# FInk.net
KiCad netlist of a schematic drawn in Altium Designer
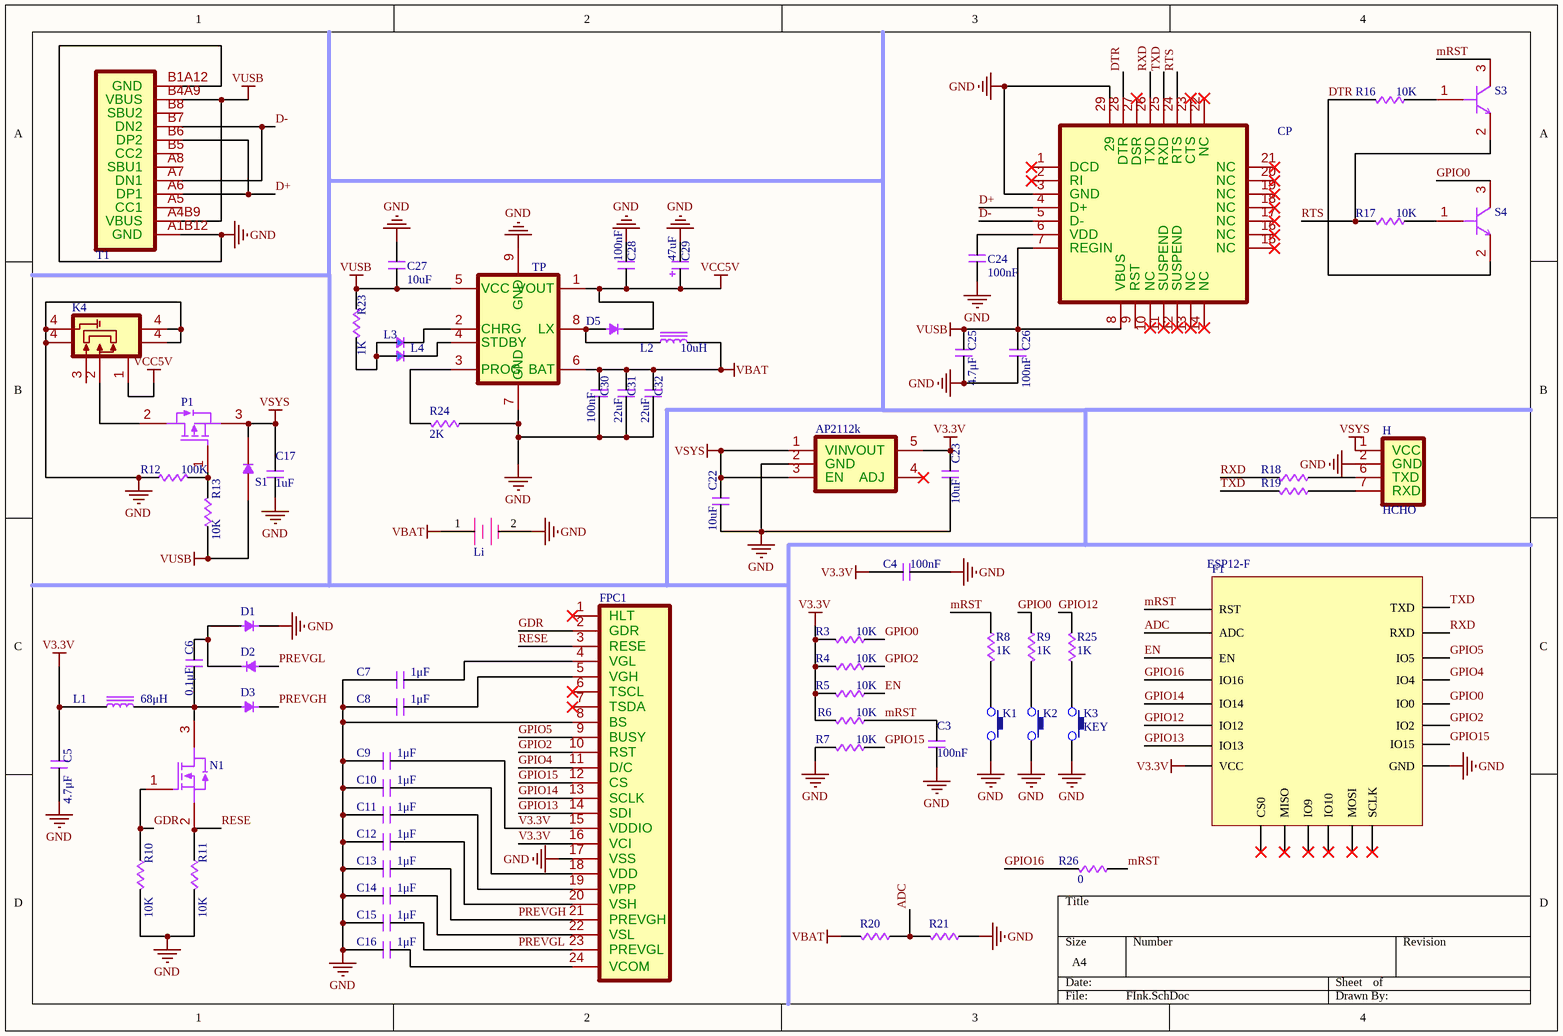
[diagram p0: FInk.SchDoc]

(export (version "E")
  (design (tool "Eeschema 10.0.6"))
  (components
    (comp (ref "AP2112k")
      (value "SPX3819 电源芯片")
      (footprint "SOT_23_SPX3819")
      (libsource (lib "Integrated_Library") (part "SPX3819 电源芯片"))
    )
    (comp (ref "C3")
      (value "100nF")
      (footprint "0603_C")
      (fields (field (name "Comment") "0603_C"))
      (libsource (lib "") (part "0603_C_1"))
    )
    (comp (ref "C4")
      (value "100nF")
      (footprint "0603_C")
      (fields (field (name "Comment") "0603_C"))
      (libsource (lib "Integrated_Library") (part "0603_C"))
    )
    (comp (ref "C5")
      (value "4.7μF")
      (footprint "0603_C")
      (fields (field (name "Comment") "0603_C"))
      (libsource (lib "") (part "0603_C_1"))
    )
    (comp (ref "C6")
      (value "0.1μF")
      (footprint "0603_C")
      (fields (field (name "Comment") "0603_C"))
      (libsource (lib "") (part "0603_C_1"))
    )
    (comp (ref "C7")
      (value "1μF")
      (footprint "0603_C")
      (fields (field (name "Comment") "0603_C"))
      (libsource (lib "Integrated_Library") (part "0603_C"))
    )
    (comp (ref "C8")
      (value "1μF")
      (footprint "0603_C")
      (fields (field (name "Comment") "0603_C"))
      (libsource (lib "Integrated_Library") (part "0603_C"))
    )
    (comp (ref "C9")
      (value "1μF")
      (footprint "0603_C")
      (fields (field (name "Comment") "0603_C"))
      (libsource (lib "Integrated_Library") (part "0603_C"))
    )
    (comp (ref "C10")
      (value "1μF")
      (footprint "0603_C")
      (fields (field (name "Comment") "0603_C"))
      (libsource (lib "Integrated_Library") (part "0603_C"))
    )
    (comp (ref "C11")
      (value "1μF")
      (footprint "0603_C")
      (fields (field (name "Comment") "0603_C"))
      (libsource (lib "Integrated_Library") (part "0603_C"))
    )
    (comp (ref "C12")
      (value "1μF")
      (footprint "0603_C")
      (fields (field (name "Comment") "0603_C"))
      (libsource (lib "Integrated_Library") (part "0603_C"))
    )
    (comp (ref "C13")
      (value "1μF")
      (footprint "0603_C")
      (fields (field (name "Comment") "0603_C"))
      (libsource (lib "Integrated_Library") (part "0603_C"))
    )
    (comp (ref "C14")
      (value "1μF")
      (footprint "0603_C")
      (fields (field (name "Comment") "0603_C"))
      (libsource (lib "Integrated_Library") (part "0603_C"))
    )
    (comp (ref "C15")
      (value "1μF")
      (footprint "0603_C")
      (fields (field (name "Comment") "0603_C"))
      (libsource (lib "Integrated_Library") (part "0603_C"))
    )
    (comp (ref "C16")
      (value "1μF")
      (footprint "0603_C")
      (fields (field (name "Comment") "0603_C"))
      (libsource (lib "Integrated_Library") (part "0603_C"))
    )
    (comp (ref "C17")
      (value "1uF")
      (footprint "0603_C")
      (fields (field (name "Comment") "0603_C"))
      (libsource (lib "") (part "0603_C_1"))
    )
    (comp (ref "C22")
      (value "10uF")
      (footprint "0603_C")
      (fields (field (name "Comment") "0603_C"))
      (libsource (lib "") (part "0603_C_1"))
    )
    (comp (ref "C23")
      (value "10uF")
      (footprint "0603_C")
      (fields (field (name "Comment") "0603_C"))
      (libsource (lib "") (part "0603_C_1"))
    )
    (comp (ref "C24")
      (value "100nF")
      (footprint "0603_C")
      (fields (field (name "Comment") "0603_C"))
      (libsource (lib "") (part "0603_C_1"))
    )
    (comp (ref "C25")
      (value "4.7μF")
      (footprint "0603_C")
      (fields (field (name "Comment") "0603_C"))
      (libsource (lib "") (part "0603_C_1"))
    )
    (comp (ref "C26")
      (value "100nF")
      (footprint "0603_C")
      (fields (field (name "Comment") "0603_C"))
      (libsource (lib "") (part "0603_C_1"))
    )
    (comp (ref "C27")
      (value "10uF")
      (footprint "0603_C")
      (fields (field (name "Comment") "0603_C"))
      (libsource (lib "") (part "0603_C_1"))
    )
    (comp (ref "C28")
      (value "100nF")
      (footprint "0603_C")
      (fields (field (name "Comment") "0603_C"))
      (libsource (lib "") (part "0603_C_1"))
    )
    (comp (ref "C29")
      (value "47uF")
      (footprint "A_CASE_c")
      (fields (field (name "Comment") "A_CASE_C"))
      (libsource (lib "Integrated_Library") (part "A_CASE_C"))
    )
    (comp (ref "C30")
      (value "100nF")
      (footprint "0603_C")
      (fields (field (name "Comment") "0603_C"))
      (libsource (lib "") (part "0603_C_1"))
    )
    (comp (ref "C31")
      (value "22uF")
      (footprint "0603_C")
      (fields (field (name "Comment") "0603_C"))
      (libsource (lib "") (part "0603_C_1"))
    )
    (comp (ref "C32")
      (value "22uF")
      (footprint "0603_C")
      (fields (field (name "Comment") "0603_C"))
      (libsource (lib "") (part "0603_C_1"))
    )
    (comp (ref "CP")
      (value "CP2102")
      (footprint "CP2102")
      (libsource (lib "Integrated_Library") (part "CP2102"))
    )
    (comp (ref "D1")
      (value "MBR0530")
      (footprint "SOD-123")
      (libsource (lib "Integrated_Library") (part "SOD_123(肖基特二极管）"))
    )
    (comp (ref "D2") (value "MBR0530") (footprint "SOD-123") (libsource (lib "") (part "SOD_123(肖基特二极管）_1")))
    (comp (ref "D3")
      (value "MBR0530")
      (footprint "SOD-123")
      (libsource (lib "Integrated_Library") (part "SOD_123(肖基特二极管）"))
    )
    (comp (ref "D5")
      (value "SMA(SS32)")
      (footprint "SMA(ss32)")
      (libsource (lib "Integrated_Library") (part "SMA(SS32)"))
    )
    (comp (ref "F1")
      (value "ESP12-F")
      (footprint "ESP-12F")
      (libsource (lib "Integrated_Library") (part "ESP_12_E"))
    )
    (comp (ref "FPC1")
      (value "CONECT")
      (footprint "FPC 24PIN")
      (libsource (lib "Integrated_Library") (part "24PIN CONNECT"))
    )
    (comp (ref "H") (value "HCHO") (footprint "HCHO") (libsource (lib "Integrated_Library") (part "HCHO")))
    (comp (ref "K1") (value "KEY") (footprint "KEY") (libsource (lib "Integrated_Library") (part "KEY")))
    (comp (ref "K2") (value "K2") (footprint "KEY") (libsource (lib "Integrated_Library") (part "KEY")))
    (comp (ref "K3") (value "KEY") (footprint "KEY") (libsource (lib "Integrated_Library") (part "KEY")))
    (comp (ref "K4")
      (value "Key")
      (footprint "MS_key")
      (libsource (lib "Integrated_Library") (part "MSK12C02"))
    )
    (comp (ref "L1")
      (value "68μH")
      (footprint "CDRH4D18")
      (fields (field (name "Comment") "SMD_H"))
      (libsource (lib "Integrated_Library") (part "SMD_H( 电感）"))
    )
    (comp (ref "L2")
      (value "10uH")
      (footprint "CDRH4D18")
      (fields (field (name "Comment") "SMD_H"))
      (libsource (lib "Integrated_Library") (part "SMD_H( 电感）"))
    )
    (comp (ref "L3")
      (value "0603_L")
      (footprint "0603_LED")
      (libsource (lib "Integrated_Library") (part "0603_LED"))
    )
    (comp (ref "L4")
      (value "0603_L")
      (footprint "0603_LED")
      (libsource (lib "Integrated_Library") (part "0603_LED"))
    )
    (comp (ref "Li") (value "Li_Po") (footprint "Li_Po") (libsource (lib "Integrated_Library") (part "LIPO")))
    (comp (ref "N1")
      (value "NMOS")
      (footprint "SOT-23-3")
      (libsource (lib "Integrated_Library") (part "NMOS"))
    )
    (comp (ref "P1") (value "PMOS") (footprint "PMOS") (libsource (lib "Integrated_Library") (part "PMOS")))
    (comp (ref "R3")
      (value "10K")
      (footprint "0603_R")
      (fields (field (name "Comment") "0603_R"))
      (libsource (lib "Integrated_Library") (part "0603_R"))
    )
    (comp (ref "R4")
      (value "10K")
      (footprint "0603_R")
      (fields (field (name "Comment") "0603_R"))
      (libsource (lib "Integrated_Library") (part "0603_R"))
    )
    (comp (ref "R5")
      (value "10K")
      (footprint "0603_R")
      (fields (field (name "Comment") "0603_R"))
      (libsource (lib "Integrated_Library") (part "0603_R"))
    )
    (comp (ref "R6")
      (value "10K")
      (footprint "0603_R")
      (fields (field (name "Comment") "0603_R"))
      (libsource (lib "Integrated_Library") (part "0603_R"))
    )
    (comp (ref "R7")
      (value "10K")
      (footprint "0603_R")
      (fields (field (name "Comment") "0603_R"))
      (libsource (lib "Integrated_Library") (part "0603_R"))
    )
    (comp (ref "R8")
      (value "1K")
      (footprint "0603_R")
      (fields (field (name "Comment") "0603_R"))
      (libsource (lib "") (part "0603_R_2"))
    )
    (comp (ref "R9")
      (value "1K")
      (footprint "0603_R")
      (fields (field (name "Comment") "0603_R"))
      (libsource (lib "") (part "0603_R_2"))
    )
    (comp (ref "R10")
      (value "10K")
      (footprint "0603_R")
      (fields (field (name "Comment") "0603_R"))
      (libsource (lib "") (part "0603_R_3"))
    )
    (comp (ref "R11")
      (value "10K")
      (footprint "0603_R")
      (fields (field (name "Comment") "0603_R"))
      (libsource (lib "") (part "0603_R_3"))
    )
    (comp (ref "R12")
      (value "100K")
      (footprint "0603_R")
      (fields (field (name "Comment") "0603_R"))
      (libsource (lib "") (part "0603_R_2"))
    )
    (comp (ref "R13")
      (value "10K")
      (footprint "0603_R")
      (fields (field (name "Comment") "0603_R"))
      (libsource (lib "") (part "0603_R_1"))
    )
    (comp (ref "R16")
      (value "10K")
      (footprint "0603_R")
      (fields (field (name "Comment") "0603_R"))
      (libsource (lib "Integrated_Library") (part "0603_R"))
    )
    (comp (ref "R17")
      (value "10K")
      (footprint "0603_R")
      (fields (field (name "Comment") "0603_R"))
      (libsource (lib "Integrated_Library") (part "0603_R"))
    )
    (comp (ref "R18") (value "0603_R") (footprint "0603_R") (libsource (lib "") (part "0603_R_1")))
    (comp (ref "R19") (value "0603_R") (footprint "0603_R") (libsource (lib "") (part "0603_R_1")))
    (comp (ref "R20") (value "0603_R") (footprint "0603_R") (libsource (lib "") (part "0603_R_1")))
    (comp (ref "R21")
      (value "0603_R")
      (footprint "0603_R")
      (libsource (lib "Integrated_Library") (part "0603_R"))
    )
    (comp (ref "R23")
      (value "1K")
      (footprint "0603_R")
      (fields (field (name "Comment") "0603_R"))
      (libsource (lib "") (part "0603_R_2"))
    )
    (comp (ref "R24")
      (value "2K")
      (footprint "0603_R")
      (fields (field (name "Comment") "0603_R"))
      (libsource (lib "Integrated_Library") (part "0603_R"))
    )
    (comp (ref "R25")
      (value "1K")
      (footprint "0603_R")
      (fields (field (name "Comment") "0603_R"))
      (libsource (lib "") (part "0603_R_1"))
    )
    (comp (ref "R26")
      (value "0")
      (footprint "0603_R")
      (fields (field (name "Comment") "0603_R"))
      (libsource (lib "Integrated_Library") (part "0603_R"))
    )
    (comp (ref "S1")
      (value "SOD323")
      (footprint "SOD-123")
      (libsource (lib "Integrated_Library") (part "SOD323"))
    )
    (comp (ref "S3") (value "NPN") (footprint "SOT-23-3") (libsource (lib "Integrated_Library") (part "NPN")))
    (comp (ref "S4") (value "NPN") (footprint "SOT-23-3") (libsource (lib "Integrated_Library") (part "NPN")))
    (comp (ref "T1")
      (value "typec")
      (footprint "TYPEC")
      (libsource (lib "Integrated_Library") (part "TYPE-C"))
    )
    (comp (ref "TP")
      (value "TP5400")
      (footprint "SOIC8")
      (libsource (lib "Integrated_Library") (part "TP5400(SOIC8)"))
    )
  )
  (nets
    (net (code "1") (name "/ADC") (class "Default")
      (node (ref "F1") (pin "2") (pinfunction "ADC_2") (pintype "passive"))
      (node (ref "R20") (pin "2") (pintype "passive"))
      (node (ref "R21") (pin "1") (pintype "passive"))
    )
    (net (code "2") (name "/D+") (class "Default")
      (node (ref "CP") (pin "4") (pinfunction "D+_4") (pintype "passive"))
      (node (ref "T1") (pin "A6") (pinfunction "DP1_A6") (pintype "passive"))
      (node (ref "T1") (pin "B6") (pinfunction "DP2_B6") (pintype "passive"))
    )
    (net (code "3") (name "/D-") (class "Default")
      (node (ref "CP") (pin "5") (pinfunction "D-_5") (pintype "passive"))
      (node (ref "T1") (pin "A7") (pinfunction "DN1_A7") (pintype "passive"))
      (node (ref "T1") (pin "B7") (pinfunction "DN2_B7") (pintype "passive"))
    )
    (net (code "4") (name "/DTR") (class "Default")
      (node (ref "CP") (pin "28") (pinfunction "DTR_28") (pintype "passive"))
      (node (ref "R16") (pin "1") (pintype "passive"))
      (node (ref "S4") (pin "2") (pinfunction "E_2") (pintype "passive"))
    )
    (net (code "5") (name "/EN") (class "Default")
      (node (ref "F1") (pin "3") (pinfunction "EN_3") (pintype "passive"))
      (node (ref "R5") (pin "2") (pintype "passive"))
    )
    (net (code "6") (name "/GDR") (class "Default")
      (node (ref "FPC1") (pin "2") (pinfunction "GDR_2") (pintype "passive"))
      (node (ref "N1") (pin "1") (pinfunction "G_1") (pintype "passive"))
      (node (ref "R10") (pin "2") (pintype "passive"))
    )
    (net (code "7") (name "/GPIO0") (class "Default")
      (node (ref "F1") (pin "18") (pinfunction "IO0_18") (pintype "passive"))
      (node (ref "R3") (pin "2") (pintype "passive"))
      (node (ref "R9") (pin "2") (pintype "passive"))
      (node (ref "S4") (pin "3") (pinfunction "C_3") (pintype "passive"))
    )
    (net (code "8") (name "/GPIO2") (class "Default")
      (node (ref "F1") (pin "17") (pinfunction "IO2_17") (pintype "passive"))
      (node (ref "FPC1") (pin "10") (pinfunction "RST_10") (pintype "passive"))
      (node (ref "R4") (pin "2") (pintype "passive"))
    )
    (net (code "9") (name "/GPIO4") (class "Default")
      (node (ref "F1") (pin "19") (pinfunction "IO4_19") (pintype "passive"))
      (node (ref "FPC1") (pin "11") (pinfunction "D/C_11") (pintype "passive"))
    )
    (net (code "10") (name "/GPIO5") (class "Default")
      (node (ref "F1") (pin "20") (pinfunction "IO5_20") (pintype "passive"))
      (node (ref "FPC1") (pin "9") (pinfunction "BUSY_9") (pintype "passive"))
    )
    (net (code "11") (name "/GPIO12") (class "Default")
      (node (ref "F1") (pin "6") (pinfunction "IO12_6") (pintype "passive"))
      (node (ref "R25") (pin "1") (pintype "passive"))
    )
    (net (code "12") (name "/GPIO13") (class "Default")
      (node (ref "F1") (pin "7") (pinfunction "IO13_7") (pintype "passive"))
      (node (ref "FPC1") (pin "14") (pinfunction "SDI_14") (pintype "passive"))
    )
    (net (code "13") (name "/GPIO14") (class "Default")
      (node (ref "F1") (pin "5") (pinfunction "IO14_5") (pintype "passive"))
      (node (ref "FPC1") (pin "13") (pinfunction "SCLK_13") (pintype "passive"))
    )
    (net (code "14") (name "/GPIO15") (class "Default")
      (node (ref "F1") (pin "16") (pinfunction "IO15_16") (pintype "passive"))
      (node (ref "FPC1") (pin "12") (pinfunction "CS_12") (pintype "passive"))
      (node (ref "R7") (pin "2") (pintype "passive"))
    )
    (net (code "15") (name "/GPIO16") (class "Default")
      (node (ref "F1") (pin "4") (pinfunction "IO16_4") (pintype "passive"))
      (node (ref "R26") (pin "1") (pintype "passive"))
    )
    (net (code "16") (name "/PREVGH") (class "Default")
      (node (ref "C13") (pin "2") (pintype "passive"))
      (node (ref "D3") (pin "2") (pintype "passive"))
      (node (ref "FPC1") (pin "21") (pinfunction "PREVGH_21") (pintype "passive"))
    )
    (net (code "17") (name "/PREVGL") (class "Default")
      (node (ref "C15") (pin "2") (pintype "passive"))
      (node (ref "D2") (pin "1") (pintype "passive"))
      (node (ref "FPC1") (pin "23") (pinfunction "PREVGL_23") (pintype "passive"))
    )
    (net (code "18") (name "/RESE") (class "Default")
      (node (ref "FPC1") (pin "3") (pinfunction "RESE_3") (pintype "passive"))
      (node (ref "N1") (pin "2") (pinfunction "S_2") (pintype "passive"))
      (node (ref "R11") (pin "2") (pintype "passive"))
    )
    (net (code "19") (name "/RTS") (class "Default")
      (node (ref "CP") (pin "24") (pinfunction "RTS_24") (pintype "passive"))
      (node (ref "R17") (pin "1") (pintype "passive"))
      (node (ref "S3") (pin "2") (pinfunction "E_2") (pintype "passive"))
    )
    (net (code "20") (name "/RXD") (class "Default")
      (node (ref "CP") (pin "26") (pinfunction "TXD_26") (pintype "passive"))
      (node (ref "F1") (pin "21") (pinfunction "RXD_21") (pintype "passive"))
      (node (ref "R18") (pin "1") (pintype "passive"))
    )
    (net (code "21") (name "/TXD") (class "Default")
      (node (ref "CP") (pin "25") (pinfunction "RXD_25") (pintype "passive"))
      (node (ref "F1") (pin "22") (pinfunction "TXD_22") (pintype "passive"))
      (node (ref "R19") (pin "1") (pintype "passive"))
    )
    (net (code "22") (name "/mRST") (class "Default")
      (node (ref "C3") (pin "2") (pintype "passive"))
      (node (ref "F1") (pin "1") (pinfunction "RST_1") (pintype "passive"))
      (node (ref "R26") (pin "2") (pintype "passive"))
      (node (ref "R6") (pin "2") (pintype "passive"))
      (node (ref "R8") (pin "2") (pintype "passive"))
      (node (ref "S3") (pin "3") (pinfunction "C_3") (pintype "passive"))
    )
    (net (code "23") (name "GND") (class "Default")
      (node (ref "AP2112k") (pin "2") (pinfunction "GND_2") (pintype "passive"))
      (node (ref "C10") (pin "1") (pintype "passive"))
      (node (ref "C11") (pin "1") (pintype "passive"))
      (node (ref "C12") (pin "1") (pintype "passive"))
      (node (ref "C13") (pin "1") (pintype "passive"))
      (node (ref "C14") (pin "1") (pintype "passive"))
      (node (ref "C15") (pin "1") (pintype "passive"))
      (node (ref "C16") (pin "1") (pintype "passive"))
      (node (ref "C17") (pin "1") (pintype "passive"))
      (node (ref "C22") (pin "1") (pintype "passive"))
      (node (ref "C23") (pin "1") (pintype "passive"))
      (node (ref "C24") (pin "1") (pintype "passive"))
      (node (ref "C25") (pin "1") (pintype "passive"))
      (node (ref "C26") (pin "1") (pintype "passive"))
      (node (ref "C27") (pin "2") (pintype "passive"))
      (node (ref "C28") (pin "2") (pintype "passive"))
      (node (ref "C29") (pin "2") (pintype "passive"))
      (node (ref "C3") (pin "1") (pintype "passive"))
      (node (ref "C30") (pin "1") (pintype "passive"))
      (node (ref "C31") (pin "1") (pintype "passive"))
      (node (ref "C32") (pin "1") (pintype "passive"))
      (node (ref "C4") (pin "2") (pintype "passive"))
      (node (ref "C5") (pin "1") (pintype "passive"))
      (node (ref "C7") (pin "1") (pintype "passive"))
      (node (ref "C8") (pin "1") (pintype "passive"))
      (node (ref "C9") (pin "1") (pintype "passive"))
      (node (ref "CP") (pin "29") (pinfunction "29_29") (pintype "passive"))
      (node (ref "CP") (pin "3") (pinfunction "GND_3") (pintype "passive"))
      (node (ref "D1") (pin "2") (pintype "passive"))
      (node (ref "F1") (pin "15") (pinfunction "GND_15") (pintype "passive"))
      (node (ref "FPC1") (pin "17") (pinfunction "VSS_17") (pintype "passive"))
      (node (ref "FPC1") (pin "8") (pinfunction "BS_8") (pintype "passive"))
      (node (ref "H") (pin "2") (pinfunction "GND_2") (pintype "passive"))
      (node (ref "K1") (pin "2") (pinfunction "2_2") (pintype "passive"))
      (node (ref "K2") (pin "2") (pinfunction "2_2") (pintype "passive"))
      (node (ref "K3") (pin "2") (pinfunction "2_2") (pintype "passive"))
      (node (ref "K4") (pin "4") (pinfunction "4_4") (pintype "passive"))
      (node (ref "Li") (pin "2") (pinfunction "-_2") (pintype "passive"))
      (node (ref "R10") (pin "1") (pintype "passive"))
      (node (ref "R11") (pin "1") (pintype "passive"))
      (node (ref "R12") (pin "2") (pintype "passive"))
      (node (ref "R21") (pin "2") (pintype "passive"))
      (node (ref "R24") (pin "2") (pintype "passive"))
      (node (ref "R7") (pin "1") (pintype "passive"))
      (node (ref "T1") (pin "A1B12") (pinfunction "GND_A1B12") (pintype "passive"))
      (node (ref "T1") (pin "B1A12") (pinfunction "GND_B1A12") (pintype "passive"))
      (node (ref "TP") (pin "7") (pinfunction "GND_7") (pintype "tri_state"))
      (node (ref "TP") (pin "9") (pinfunction "GND_9") (pintype "tri_state"))
    )
    (net (code "24") (name "Net-(C6-Pad2)") (class "Default")
      (node (ref "C6") (pin "2") (pintype "passive"))
      (node (ref "D1") (pin "1") (pintype "passive"))
      (node (ref "D2") (pin "2") (pintype "passive"))
    )
    (net (code "25") (name "Net-(CP-VDD)") (class "Default")
      (node (ref "C24") (pin "2") (pintype "passive"))
      (node (ref "CP") (pin "6") (pinfunction "VDD_6") (pintype "passive"))
    )
    (net (code "26") (name "Net-(FPC1-VCOM)") (class "Default")
      (node (ref "C16") (pin "2") (pintype "passive"))
      (node (ref "FPC1") (pin "24") (pinfunction "VCOM_24") (pintype "passive"))
    )
    (net (code "27") (name "Net-(FPC1-VDD)") (class "Default")
      (node (ref "C10") (pin "2") (pintype "passive"))
      (node (ref "FPC1") (pin "18") (pinfunction "VDD_18") (pintype "passive"))
    )
    (net (code "28") (name "Net-(FPC1-VGH)") (class "Default")
      (node (ref "C8") (pin "2") (pintype "passive"))
      (node (ref "FPC1") (pin "5") (pinfunction "VGH_5") (pintype "passive"))
    )
    (net (code "29") (name "Net-(FPC1-VGL)") (class "Default")
      (node (ref "C7") (pin "2") (pintype "passive"))
      (node (ref "FPC1") (pin "4") (pinfunction "VGL_4") (pintype "passive"))
    )
    (net (code "30") (name "Net-(FPC1-VPP)") (class "Default")
      (node (ref "C11") (pin "2") (pintype "passive"))
      (node (ref "FPC1") (pin "19") (pinfunction "VPP_19") (pintype "passive"))
    )
    (net (code "31") (name "Net-(FPC1-VSH)") (class "Default")
      (node (ref "C12") (pin "2") (pintype "passive"))
      (node (ref "FPC1") (pin "20") (pinfunction "VSH_20") (pintype "passive"))
    )
    (net (code "32") (name "Net-(FPC1-VSL)") (class "Default")
      (node (ref "C14") (pin "2") (pintype "passive"))
      (node (ref "FPC1") (pin "22") (pinfunction "VSL_22") (pintype "passive"))
    )
    (net (code "33") (name "Net-(H-RXD)") (class "Default")
      (node (ref "H") (pin "7") (pinfunction "RXD_7") (pintype "passive"))
      (node (ref "R19") (pin "2") (pintype "passive"))
    )
    (net (code "34") (name "Net-(H-TXD)") (class "Default")
      (node (ref "H") (pin "6") (pinfunction "TXD_6") (pintype "passive"))
      (node (ref "R18") (pin "2") (pintype "passive"))
    )
    (net (code "35") (name "Net-(K1-Pad1)") (class "Default")
      (node (ref "K1") (pin "1") (pinfunction "1_1") (pintype "passive"))
      (node (ref "R8") (pin "1") (pintype "passive"))
    )
    (net (code "36") (name "Net-(K2-Pad1)") (class "Default")
      (node (ref "K2") (pin "1") (pinfunction "1_1") (pintype "passive"))
      (node (ref "R9") (pin "1") (pintype "passive"))
    )
    (net (code "37") (name "Net-(K3-Pad1)") (class "Default")
      (node (ref "K3") (pin "1") (pinfunction "1_1") (pintype "passive"))
      (node (ref "R25") (pin "2") (pintype "passive"))
    )
    (net (code "38") (name "Net-(L3-+)") (class "Default")
      (node (ref "L3") (pin "1") (pinfunction "+_1") (pintype "passive"))
      (node (ref "L4") (pin "1") (pinfunction "+_1") (pintype "passive"))
      (node (ref "R23") (pin "1") (pintype "passive"))
    )
    (net (code "39") (name "Net-(N1-D)") (class "Default")
      (node (ref "C6") (pin "1") (pintype "passive"))
      (node (ref "D3") (pin "1") (pintype "passive"))
      (node (ref "L1") (pin "2") (pintype "passive"))
      (node (ref "N1") (pin "3") (pinfunction "D_3") (pintype "passive"))
    )
    (net (code "40") (name "Net-(P1-D)") (class "Default")
      (node (ref "K4") (pin "2") (pinfunction "2_2") (pintype "passive"))
      (node (ref "P1") (pin "2") (pinfunction "D_2") (pintype "passive"))
    )
    (net (code "41") (name "Net-(P1-G)") (class "Default")
      (node (ref "P1") (pin "1") (pinfunction "G_1") (pintype "passive"))
      (node (ref "R12") (pin "1") (pintype "passive"))
      (node (ref "R13") (pin "1") (pintype "passive"))
    )
    (net (code "42") (name "Net-(S3-B)") (class "Default")
      (node (ref "R16") (pin "2") (pintype "passive"))
      (node (ref "S3") (pin "1") (pinfunction "B_1") (pintype "passive"))
    )
    (net (code "43") (name "Net-(S4-B)") (class "Default")
      (node (ref "R17") (pin "2") (pintype "passive"))
      (node (ref "S4") (pin "1") (pinfunction "B_1") (pintype "passive"))
    )
    (net (code "44") (name "Net-(TP-CHRG)") (class "Default")
      (node (ref "L3") (pin "2") (pintype "passive"))
      (node (ref "TP") (pin "2") (pinfunction "CHRG_2") (pintype "tri_state"))
    )
    (net (code "45") (name "Net-(TP-LX)") (class "Default")
      (node (ref "D5") (pin "1") (pintype "passive"))
      (node (ref "L2") (pin "1") (pintype "passive"))
      (node (ref "TP") (pin "8") (pinfunction "LX_8") (pintype "tri_state"))
    )
    (net (code "46") (name "Net-(TP-PROG)") (class "Default")
      (node (ref "R24") (pin "1") (pintype "passive"))
      (node (ref "TP") (pin "3") (pinfunction "PROG_3") (pintype "tri_state"))
    )
    (net (code "47") (name "Net-(TP-STDBY)") (class "Default")
      (node (ref "L4") (pin "2") (pintype "passive"))
      (node (ref "TP") (pin "4") (pinfunction "STDBY_4") (pintype "tri_state"))
    )
    (net (code "48") (name "V3.3V") (class "Default")
      (node (ref "AP2112k") (pin "5") (pinfunction "VOUT_5") (pintype "passive"))
      (node (ref "C23") (pin "2") (pintype "passive"))
      (node (ref "C4") (pin "1") (pintype "passive"))
      (node (ref "C5") (pin "2") (pintype "passive"))
      (node (ref "C9") (pin "2") (pintype "passive"))
      (node (ref "F1") (pin "8") (pinfunction "VCC_8") (pintype "passive"))
      (node (ref "FPC1") (pin "15") (pinfunction "VDDIO_15") (pintype "passive"))
      (node (ref "FPC1") (pin "16") (pinfunction "VCI_16") (pintype "passive"))
      (node (ref "L1") (pin "1") (pintype "passive"))
      (node (ref "R3") (pin "1") (pintype "passive"))
      (node (ref "R4") (pin "1") (pintype "passive"))
      (node (ref "R5") (pin "1") (pintype "passive"))
      (node (ref "R6") (pin "1") (pintype "passive"))
    )
    (net (code "49") (name "VBAT") (class "Default")
      (node (ref "C30") (pin "2") (pintype "passive"))
      (node (ref "C31") (pin "2") (pintype "passive"))
      (node (ref "C32") (pin "2") (pintype "passive"))
      (node (ref "L2") (pin "2") (pintype "passive"))
      (node (ref "Li") (pin "1") (pinfunction "+_1") (pintype "passive"))
      (node (ref "R20") (pin "1") (pintype "passive"))
      (node (ref "TP") (pin "6") (pinfunction "BAT_6") (pintype "tri_state"))
    )
    (net (code "50") (name "VCC5V") (class "Default")
      (node (ref "C28") (pin "1") (pintype "passive"))
      (node (ref "C29") (pin "1") (pintype "passive"))
      (node (ref "D5") (pin "2") (pintype "passive"))
      (node (ref "K4") (pin "1") (pinfunction "1_1") (pintype "passive"))
      (node (ref "TP") (pin "1") (pinfunction "VOUT_1") (pintype "tri_state"))
    )
    (net (code "51") (name "VSYS") (class "Default")
      (node (ref "AP2112k") (pin "1") (pinfunction "VIN_1") (pintype "passive"))
      (node (ref "AP2112k") (pin "3") (pinfunction "EN_3") (pintype "passive"))
      (node (ref "C17") (pin "2") (pintype "passive"))
      (node (ref "C22") (pin "2") (pintype "passive"))
      (node (ref "H") (pin "1") (pinfunction "VCC_1") (pintype "passive"))
      (node (ref "P1") (pin "3") (pinfunction "S_3") (pintype "passive"))
      (node (ref "S1") (pin "2") (pinfunction "2_2") (pintype "passive"))
    )
    (net (code "52") (name "VUSB") (class "Default")
      (node (ref "C25") (pin "2") (pintype "passive"))
      (node (ref "C26") (pin "2") (pintype "passive"))
      (node (ref "C27") (pin "1") (pintype "passive"))
      (node (ref "CP") (pin "7") (pinfunction "REGIN_7") (pintype "passive"))
      (node (ref "CP") (pin "8") (pinfunction "VBUS_8") (pintype "passive"))
      (node (ref "R13") (pin "2") (pintype "passive"))
      (node (ref "R23") (pin "2") (pintype "passive"))
      (node (ref "S1") (pin "1") (pinfunction "1_1") (pintype "passive"))
      (node (ref "T1") (pin "A4B9") (pinfunction "VBUS_A4B9") (pintype "passive"))
      (node (ref "T1") (pin "B4A9") (pinfunction "VBUS_B4A9") (pintype "passive"))
      (node (ref "TP") (pin "5") (pinfunction "VCC_5") (pintype "tri_state"))
    )
    (net (code "53") (name "unconnected-(AP2112k-ADJ-Pad4)") (class "Default")
      (node (ref "AP2112k") (pin "4") (pinfunction "ADJ_4") (pintype "passive+no_connect"))
    )
    (net (code "54") (name "unconnected-(CP-CTS-Pad23)") (class "Default")
      (node (ref "CP") (pin "23") (pinfunction "CTS_23") (pintype "passive+no_connect"))
    )
    (net (code "55") (name "unconnected-(CP-DCD-Pad1)") (class "Default")
      (node (ref "CP") (pin "1") (pinfunction "DCD_1") (pintype "passive"))
    )
    (net (code "56") (name "unconnected-(CP-DSR-Pad27)") (class "Default")
      (node (ref "CP") (pin "27") (pinfunction "DSR_27") (pintype "passive+no_connect"))
    )
    (net (code "57") (name "unconnected-(CP-NC-Pad10)") (class "Default")
      (node (ref "CP") (pin "10") (pinfunction "NC_10") (pintype "passive+no_connect"))
    )
    (net (code "58") (name "unconnected-(CP-NC-Pad13)") (class "Default")
      (node (ref "CP") (pin "13") (pinfunction "NC_13") (pintype "passive+no_connect"))
    )
    (net (code "59") (name "unconnected-(CP-NC-Pad14)") (class "Default")
      (node (ref "CP") (pin "14") (pinfunction "NC_14") (pintype "passive+no_connect"))
    )
    (net (code "60") (name "unconnected-(CP-NC-Pad15)") (class "Default")
      (node (ref "CP") (pin "15") (pinfunction "NC_15") (pintype "passive+no_connect"))
    )
    (net (code "61") (name "unconnected-(CP-NC-Pad16)") (class "Default")
      (node (ref "CP") (pin "16") (pinfunction "NC_16") (pintype "passive+no_connect"))
    )
    (net (code "62") (name "unconnected-(CP-NC-Pad17)") (class "Default")
      (node (ref "CP") (pin "17") (pinfunction "NC_17") (pintype "passive+no_connect"))
    )
    (net (code "63") (name "unconnected-(CP-NC-Pad18)") (class "Default")
      (node (ref "CP") (pin "18") (pinfunction "NC_18") (pintype "passive+no_connect"))
    )
    (net (code "64") (name "unconnected-(CP-NC-Pad19)") (class "Default")
      (node (ref "CP") (pin "19") (pinfunction "NC_19") (pintype "passive+no_connect"))
    )
    (net (code "65") (name "unconnected-(CP-NC-Pad20)") (class "Default")
      (node (ref "CP") (pin "20") (pinfunction "NC_20") (pintype "passive+no_connect"))
    )
    (net (code "66") (name "unconnected-(CP-NC-Pad21)") (class "Default")
      (node (ref "CP") (pin "21") (pinfunction "NC_21") (pintype "passive+no_connect"))
    )
    (net (code "67") (name "unconnected-(CP-NC-Pad22)") (class "Default")
      (node (ref "CP") (pin "22") (pinfunction "NC_22") (pintype "passive+no_connect"))
    )
    (net (code "68") (name "unconnected-(CP-RI-Pad2)") (class "Default")
      (node (ref "CP") (pin "2") (pinfunction "RI_2") (pintype "passive"))
    )
    (net (code "69") (name "unconnected-(CP-RST-Pad9)") (class "Default")
      (node (ref "CP") (pin "9") (pinfunction "RST_9") (pintype "passive"))
    )
    (net (code "70") (name "unconnected-(CP-SUSPEND-Pad11)") (class "Default")
      (node (ref "CP") (pin "11") (pinfunction "SUSPEND_11") (pintype "passive+no_connect"))
    )
    (net (code "71") (name "unconnected-(CP-SUSPEND-Pad12)") (class "Default")
      (node (ref "CP") (pin "12") (pinfunction "SUSPEND_12") (pintype "passive+no_connect"))
    )
    (net (code "72") (name "unconnected-(F1-CS0-Pad9)") (class "Default")
      (node (ref "F1") (pin "9") (pinfunction "CS0_9") (pintype "passive+no_connect"))
    )
    (net (code "73") (name "unconnected-(F1-IO9-Pad11)") (class "Default")
      (node (ref "F1") (pin "11") (pinfunction "IO9_11") (pintype "passive+no_connect"))
    )
    (net (code "74") (name "unconnected-(F1-IO10-Pad12)") (class "Default")
      (node (ref "F1") (pin "12") (pinfunction "IO10_12") (pintype "passive+no_connect"))
    )
    (net (code "75") (name "unconnected-(F1-MISO-Pad10)") (class "Default")
      (node (ref "F1") (pin "10") (pinfunction "MISO_10") (pintype "passive+no_connect"))
    )
    (net (code "76") (name "unconnected-(F1-MOSI-Pad13)") (class "Default")
      (node (ref "F1") (pin "13") (pinfunction "MOSI_13") (pintype "passive+no_connect"))
    )
    (net (code "77") (name "unconnected-(F1-SCLK-Pad14)") (class "Default")
      (node (ref "F1") (pin "14") (pinfunction "SCLK_14") (pintype "passive+no_connect"))
    )
    (net (code "78") (name "unconnected-(FPC1-HLT-Pad1)") (class "Default")
      (node (ref "FPC1") (pin "1") (pinfunction "HLT_1") (pintype "passive+no_connect"))
    )
    (net (code "79") (name "unconnected-(FPC1-TSCL-Pad6)") (class "Default")
      (node (ref "FPC1") (pin "6") (pinfunction "TSCL_6") (pintype "passive+no_connect"))
    )
    (net (code "80") (name "unconnected-(FPC1-TSDA-Pad7)") (class "Default")
      (node (ref "FPC1") (pin "7") (pinfunction "TSDA_7") (pintype "passive+no_connect"))
    )
    (net (code "81") (name "unconnected-(K4-Pad3)") (class "Default")
      (node (ref "K4") (pin "3") (pinfunction "3_3") (pintype "passive"))
    )
    (net (code "82") (name "unconnected-(T1-CC1-PadA5)") (class "Default")
      (node (ref "T1") (pin "A5") (pinfunction "CC1_A5") (pintype "passive"))
    )
    (net (code "83") (name "unconnected-(T1-CC2-PadB5)") (class "Default")
      (node (ref "T1") (pin "B5") (pinfunction "CC2_B5") (pintype "passive"))
    )
    (net (code "84") (name "unconnected-(T1-SBU1-PadA8)") (class "Default")
      (node (ref "T1") (pin "A8") (pinfunction "SBU1_A8") (pintype "passive"))
    )
    (net (code "85") (name "unconnected-(T1-SBU2-PadB8)") (class "Default")
      (node (ref "T1") (pin "B8") (pinfunction "SBU2_B8") (pintype "passive"))
    )
  )
)
